# dr_amged.net
KiCad netlist of a schematic drawn in EAGLE
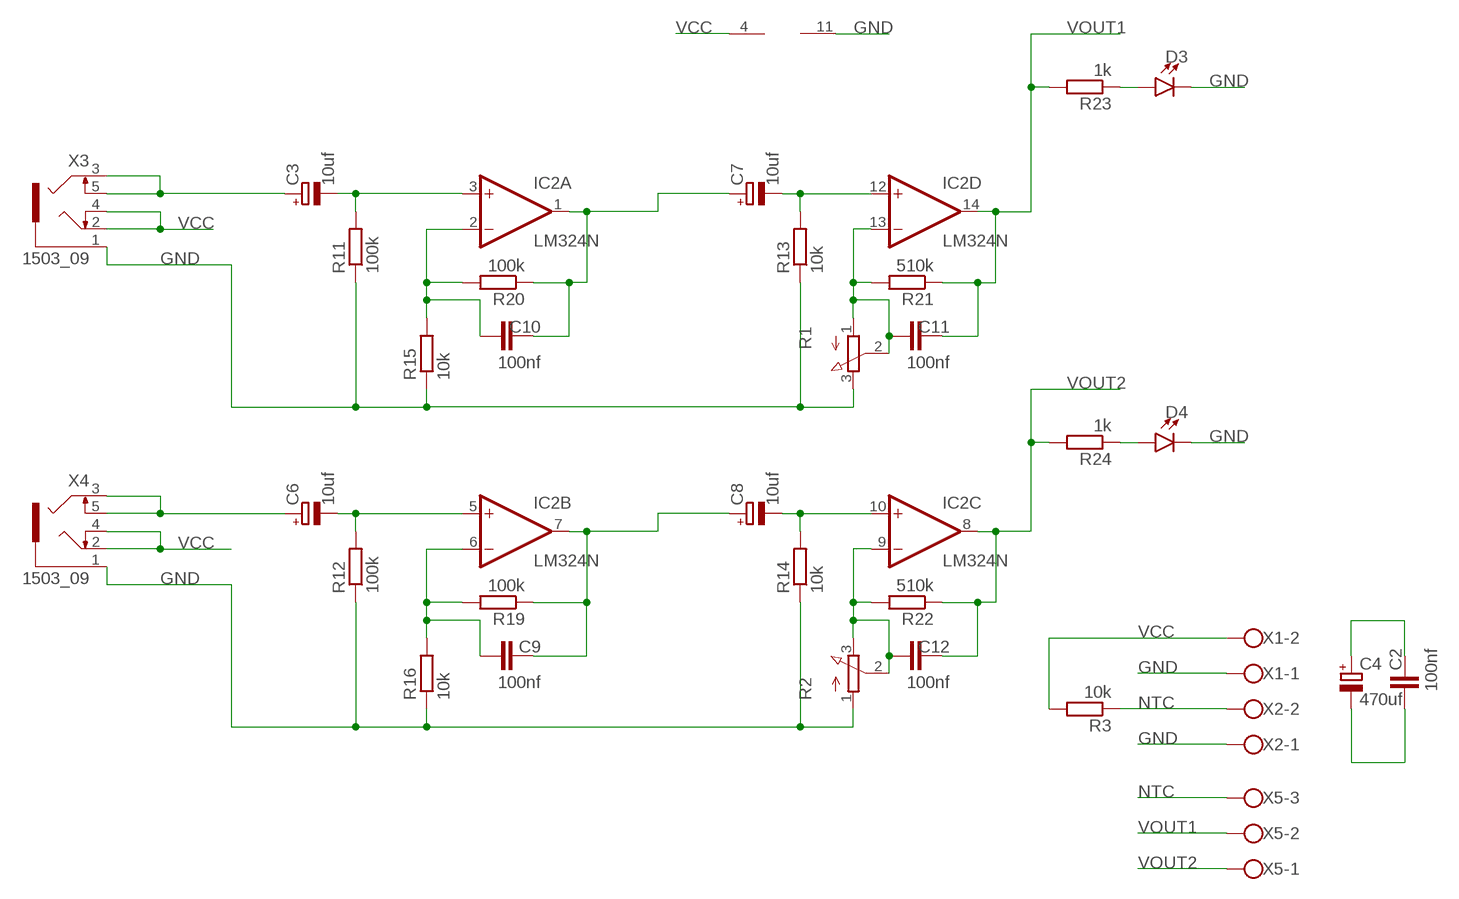
[diagram p0: schematic, sheet 1]

(export (version "E")
  (design (tool "Eeschema 10.0.6"))
  (components
    (comp (ref "C2")
      (value "100nf")
      (footprint "eagle-import:C050-030X075")
      (libsource (lib "eagle-import") (part "C-EU050-030X075"))
    )
    (comp (ref "C3")
      (value "10uf")
      (footprint "eagle-import:E2-5")
      (libsource (lib "eagle-import") (part "CPOL-EUE2-5"))
    )
    (comp (ref "C4")
      (value "470uf")
      (footprint "eagle-import:E3,5-8")
      (libsource (lib "eagle-import") (part "CPOL-EUE3.5-8"))
    )
    (comp (ref "C6")
      (value "10uf")
      (footprint "eagle-import:E2-5")
      (libsource (lib "eagle-import") (part "CPOL-EUE2-5"))
    )
    (comp (ref "C7")
      (value "10uf")
      (footprint "eagle-import:E2-5")
      (libsource (lib "eagle-import") (part "CPOL-EUE2-5"))
    )
    (comp (ref "C8")
      (value "10uf")
      (footprint "eagle-import:E2-5")
      (libsource (lib "eagle-import") (part "CPOL-EUE2-5"))
    )
    (comp (ref "C9")
      (value "100nf")
      (footprint "eagle-import:C050-030X075")
      (libsource (lib "eagle-import") (part "C-EU050-030X075"))
    )
    (comp (ref "C10")
      (value "100nf")
      (footprint "eagle-import:C050-030X075")
      (libsource (lib "eagle-import") (part "C-EU050-030X075"))
    )
    (comp (ref "C11")
      (value "100nf")
      (footprint "eagle-import:C050-030X075")
      (libsource (lib "eagle-import") (part "C-EU050-030X075"))
    )
    (comp (ref "C12")
      (value "100nf")
      (footprint "eagle-import:C050-030X075")
      (libsource (lib "eagle-import") (part "C-EU050-030X075"))
    )
    (comp (ref "D3")
      (value "LED5MM")
      (footprint "eagle-import:LED_5MM")
      (libsource (lib "eagle-import") (part "LED5MM"))
    )
    (comp (ref "D4")
      (value "LED5MM")
      (footprint "eagle-import:LED_5MM")
      (libsource (lib "eagle-import") (part "LED5MM"))
    )
    (comp (ref "IC2")
      (value "LM324N")
      (footprint "eagle-import:DIL14")
      (libsource (lib "eagle-import") (part "LM324N"))
    )
    (comp (ref "R1")
      (value "3RP/1610N")
      (footprint "eagle-import:3RP_1610N")
      (libsource (lib "eagle-import") (part "3RP/1610N"))
    )
    (comp (ref "R2")
      (value "3RP/1610N")
      (footprint "eagle-import:3RP_1610N")
      (libsource (lib "eagle-import") (part "3RP/1610N"))
    )
    (comp (ref "R3")
      (value "10k")
      (footprint "eagle-import:0207_10")
      (libsource (lib "eagle-import") (part "R-EU_0207/10"))
    )
    (comp (ref "R11")
      (value "100k")
      (footprint "eagle-import:0207_10")
      (libsource (lib "eagle-import") (part "R-EU_0207/10"))
    )
    (comp (ref "R12")
      (value "100k")
      (footprint "eagle-import:0207_10")
      (libsource (lib "eagle-import") (part "R-EU_0207/10"))
    )
    (comp (ref "R13")
      (value "10k")
      (footprint "eagle-import:0207_10")
      (libsource (lib "eagle-import") (part "R-EU_0207/10"))
    )
    (comp (ref "R14")
      (value "10k")
      (footprint "eagle-import:0207_10")
      (libsource (lib "eagle-import") (part "R-EU_0207/10"))
    )
    (comp (ref "R15")
      (value "10k")
      (footprint "eagle-import:0207_10")
      (libsource (lib "eagle-import") (part "R-EU_0207/10"))
    )
    (comp (ref "R16")
      (value "10k")
      (footprint "eagle-import:0207_10")
      (libsource (lib "eagle-import") (part "R-EU_0207/10"))
    )
    (comp (ref "R19")
      (value "100k")
      (footprint "eagle-import:0207_10")
      (libsource (lib "eagle-import") (part "R-EU_0207/10"))
    )
    (comp (ref "R20")
      (value "100k")
      (footprint "eagle-import:0207_10")
      (libsource (lib "eagle-import") (part "R-EU_0207/10"))
    )
    (comp (ref "R21")
      (value "510k")
      (footprint "eagle-import:0207_10")
      (libsource (lib "eagle-import") (part "R-EU_0207/10"))
    )
    (comp (ref "R22")
      (value "510k")
      (footprint "eagle-import:0207_10")
      (libsource (lib "eagle-import") (part "R-EU_0207/10"))
    )
    (comp (ref "R23")
      (value "1k")
      (footprint "eagle-import:0207_10")
      (libsource (lib "eagle-import") (part "R-EU_0207/10"))
    )
    (comp (ref "R24")
      (value "1k")
      (footprint "eagle-import:0207_10")
      (libsource (lib "eagle-import") (part "R-EU_0207/10"))
    )
    (comp (ref "X1")
      (value "W237-102")
      (footprint "eagle-import:W237-102")
      (fields (field (name "MPN") "237-102"))
      (libsource (lib "eagle-import") (part "W237-102"))
    )
    (comp (ref "X2")
      (value "W237-102")
      (footprint "eagle-import:W237-102")
      (fields (field (name "MPN") "237-102"))
      (libsource (lib "eagle-import") (part "W237-102"))
    )
    (comp (ref "X3")
      (value "1503_09")
      (footprint "eagle-import:1503_09")
      (libsource (lib "eagle-import") (part "1503_09"))
    )
    (comp (ref "X4")
      (value "1503_09")
      (footprint "eagle-import:1503_09")
      (libsource (lib "eagle-import") (part "1503_09"))
    )
    (comp (ref "X5")
      (value "W237-103")
      (footprint "eagle-import:W237-103")
      (fields (field (name "MPN") "237-103"))
      (libsource (lib "eagle-import") (part "W237-103"))
    )
  )
  (nets
    (net (code "1") (name "/GND") (class "Default")
      (node (ref "C2") (pin "1") (pinfunction "1_1") (pintype "passive"))
      (node (ref "C4") (pin "-") (pinfunction "-_-") (pintype "passive"))
      (node (ref "D3") (pin "K") (pinfunction "C_K") (pintype "passive"))
      (node (ref "D4") (pin "K") (pinfunction "C_K") (pintype "passive"))
      (node (ref "IC2") (pin "11") (pinfunction "V-_11") (pintype "power_in"))
      (node (ref "R1") (pin "3") (pinfunction "E_3") (pintype "passive"))
      (node (ref "R11") (pin "1") (pinfunction "1_1") (pintype "passive"))
      (node (ref "R12") (pin "1") (pinfunction "1_1") (pintype "passive"))
      (node (ref "R13") (pin "1") (pinfunction "1_1") (pintype "passive"))
      (node (ref "R14") (pin "1") (pinfunction "1_1") (pintype "passive"))
      (node (ref "R15") (pin "1") (pinfunction "1_1") (pintype "passive"))
      (node (ref "R16") (pin "1") (pinfunction "1_1") (pintype "passive"))
      (node (ref "R2") (pin "1") (pinfunction "A_1") (pintype "passive"))
      (node (ref "X1") (pin "1") (pinfunction "KL_1") (pintype "passive"))
      (node (ref "X2") (pin "1") (pinfunction "KL_1") (pintype "passive"))
      (node (ref "X3") (pin "1") (pinfunction "1_1") (pintype "passive"))
      (node (ref "X4") (pin "1") (pinfunction "1_1") (pintype "passive"))
    )
    (net (code "2") (name "/NTC") (class "Default")
      (node (ref "R3") (pin "1") (pinfunction "1_1") (pintype "passive"))
      (node (ref "X2") (pin "2") (pinfunction "KL_2") (pintype "passive"))
      (node (ref "X5") (pin "3") (pinfunction "KL_3") (pintype "passive"))
    )
    (net (code "3") (name "/VCC") (class "Default")
      (node (ref "C2") (pin "2") (pinfunction "2_2") (pintype "passive"))
      (node (ref "C4") (pin "+") (pinfunction "+_+") (pintype "passive"))
      (node (ref "IC2") (pin "4") (pinfunction "V+_4") (pintype "power_in"))
      (node (ref "R3") (pin "2") (pinfunction "2_2") (pintype "passive"))
      (node (ref "X1") (pin "2") (pinfunction "KL_2") (pintype "passive"))
      (node (ref "X3") (pin "2") (pinfunction "2_2") (pintype "passive"))
      (node (ref "X3") (pin "4") (pinfunction "4_4") (pintype "passive"))
      (node (ref "X4") (pin "2") (pinfunction "2_2") (pintype "passive"))
      (node (ref "X4") (pin "4") (pinfunction "4_4") (pintype "passive"))
    )
    (net (code "4") (name "/VOUT1") (class "Default")
      (node (ref "C11") (pin "2") (pinfunction "2_2") (pintype "passive"))
      (node (ref "IC2") (pin "14") (pinfunction "OUT_14") (pintype "output"))
      (node (ref "R21") (pin "1") (pinfunction "1_1") (pintype "passive"))
      (node (ref "R23") (pin "2") (pinfunction "2_2") (pintype "passive"))
      (node (ref "X5") (pin "2") (pinfunction "KL_2") (pintype "passive"))
    )
    (net (code "5") (name "/VOUT2") (class "Default")
      (node (ref "C12") (pin "2") (pinfunction "2_2") (pintype "passive"))
      (node (ref "IC2") (pin "8") (pinfunction "OUT_8") (pintype "output"))
      (node (ref "R22") (pin "1") (pinfunction "1_1") (pintype "passive"))
      (node (ref "R24") (pin "2") (pinfunction "2_2") (pintype "passive"))
      (node (ref "X5") (pin "1") (pinfunction "KL_1") (pintype "passive"))
    )
    (net (code "6") (name "Net-(C3-Pad+)") (class "Default")
      (node (ref "C3") (pin "+") (pinfunction "+_+") (pintype "passive"))
      (node (ref "X3") (pin "3") (pinfunction "3_3") (pintype "passive"))
      (node (ref "X3") (pin "5") (pinfunction "5_5") (pintype "passive"))
    )
    (net (code "7") (name "Net-(C6-Pad+)") (class "Default")
      (node (ref "C6") (pin "+") (pinfunction "+_+") (pintype "passive"))
      (node (ref "X4") (pin "3") (pinfunction "3_3") (pintype "passive"))
      (node (ref "X4") (pin "5") (pinfunction "5_5") (pintype "passive"))
    )
    (net (code "8") (name "Net-(D3-PadA)") (class "Default")
      (node (ref "D3") (pin "A") (pinfunction "A_A") (pintype "passive"))
      (node (ref "R23") (pin "1") (pinfunction "1_1") (pintype "passive"))
    )
    (net (code "9") (name "Net-(D4-PadA)") (class "Default")
      (node (ref "D4") (pin "A") (pinfunction "A_A") (pintype "passive"))
      (node (ref "R24") (pin "1") (pinfunction "1_1") (pintype "passive"))
    )
    (net (code "10") (name "Net-(IC2A-+IN)") (class "Default")
      (node (ref "C3") (pin "-") (pinfunction "-_-") (pintype "passive"))
      (node (ref "IC2") (pin "3") (pinfunction "+IN_3") (pintype "input"))
      (node (ref "R11") (pin "2") (pinfunction "2_2") (pintype "passive"))
    )
    (net (code "11") (name "Net-(IC2A--IN)") (class "Default")
      (node (ref "C10") (pin "1") (pinfunction "1_1") (pintype "passive"))
      (node (ref "IC2") (pin "2") (pinfunction "-IN_2") (pintype "input"))
      (node (ref "R15") (pin "2") (pinfunction "2_2") (pintype "passive"))
      (node (ref "R20") (pin "2") (pinfunction "2_2") (pintype "passive"))
    )
    (net (code "12") (name "Net-(IC2A-OUT)") (class "Default")
      (node (ref "C10") (pin "2") (pinfunction "2_2") (pintype "passive"))
      (node (ref "C7") (pin "+") (pinfunction "+_+") (pintype "passive"))
      (node (ref "IC2") (pin "1") (pinfunction "OUT_1") (pintype "output"))
      (node (ref "R20") (pin "1") (pinfunction "1_1") (pintype "passive"))
    )
    (net (code "13") (name "Net-(IC2B-+IN)") (class "Default")
      (node (ref "C6") (pin "-") (pinfunction "-_-") (pintype "passive"))
      (node (ref "IC2") (pin "5") (pinfunction "+IN_5") (pintype "input"))
      (node (ref "R12") (pin "2") (pinfunction "2_2") (pintype "passive"))
    )
    (net (code "14") (name "Net-(IC2B--IN)") (class "Default")
      (node (ref "C9") (pin "1") (pinfunction "1_1") (pintype "passive"))
      (node (ref "IC2") (pin "6") (pinfunction "-IN_6") (pintype "input"))
      (node (ref "R16") (pin "2") (pinfunction "2_2") (pintype "passive"))
      (node (ref "R19") (pin "2") (pinfunction "2_2") (pintype "passive"))
    )
    (net (code "15") (name "Net-(IC2B-OUT)") (class "Default")
      (node (ref "C8") (pin "+") (pinfunction "+_+") (pintype "passive"))
      (node (ref "C9") (pin "2") (pinfunction "2_2") (pintype "passive"))
      (node (ref "IC2") (pin "7") (pinfunction "OUT_7") (pintype "output"))
      (node (ref "R19") (pin "1") (pinfunction "1_1") (pintype "passive"))
    )
    (net (code "16") (name "Net-(IC2C-+IN)") (class "Default")
      (node (ref "C8") (pin "-") (pinfunction "-_-") (pintype "passive"))
      (node (ref "IC2") (pin "10") (pinfunction "+IN_10") (pintype "input"))
      (node (ref "R14") (pin "2") (pinfunction "2_2") (pintype "passive"))
    )
    (net (code "17") (name "Net-(IC2C--IN)") (class "Default")
      (node (ref "C12") (pin "1") (pinfunction "1_1") (pintype "passive"))
      (node (ref "IC2") (pin "9") (pinfunction "-IN_9") (pintype "input"))
      (node (ref "R2") (pin "2") (pinfunction "S_2") (pintype "passive"))
      (node (ref "R2") (pin "3") (pinfunction "E_3") (pintype "passive"))
      (node (ref "R22") (pin "2") (pinfunction "2_2") (pintype "passive"))
    )
    (net (code "18") (name "Net-(IC2D-+IN)") (class "Default")
      (node (ref "C7") (pin "-") (pinfunction "-_-") (pintype "passive"))
      (node (ref "IC2") (pin "12") (pinfunction "+IN_12") (pintype "input"))
      (node (ref "R13") (pin "2") (pinfunction "2_2") (pintype "passive"))
    )
    (net (code "19") (name "Net-(IC2D--IN)") (class "Default")
      (node (ref "C11") (pin "1") (pinfunction "1_1") (pintype "passive"))
      (node (ref "IC2") (pin "13") (pinfunction "-IN_13") (pintype "input"))
      (node (ref "R1") (pin "1") (pinfunction "A_1") (pintype "passive"))
      (node (ref "R1") (pin "2") (pinfunction "S_2") (pintype "passive"))
      (node (ref "R21") (pin "2") (pinfunction "2_2") (pintype "passive"))
    )
  )
)
